# 20717.net
KiCad netlist of a schematic drawn in Altium Designer
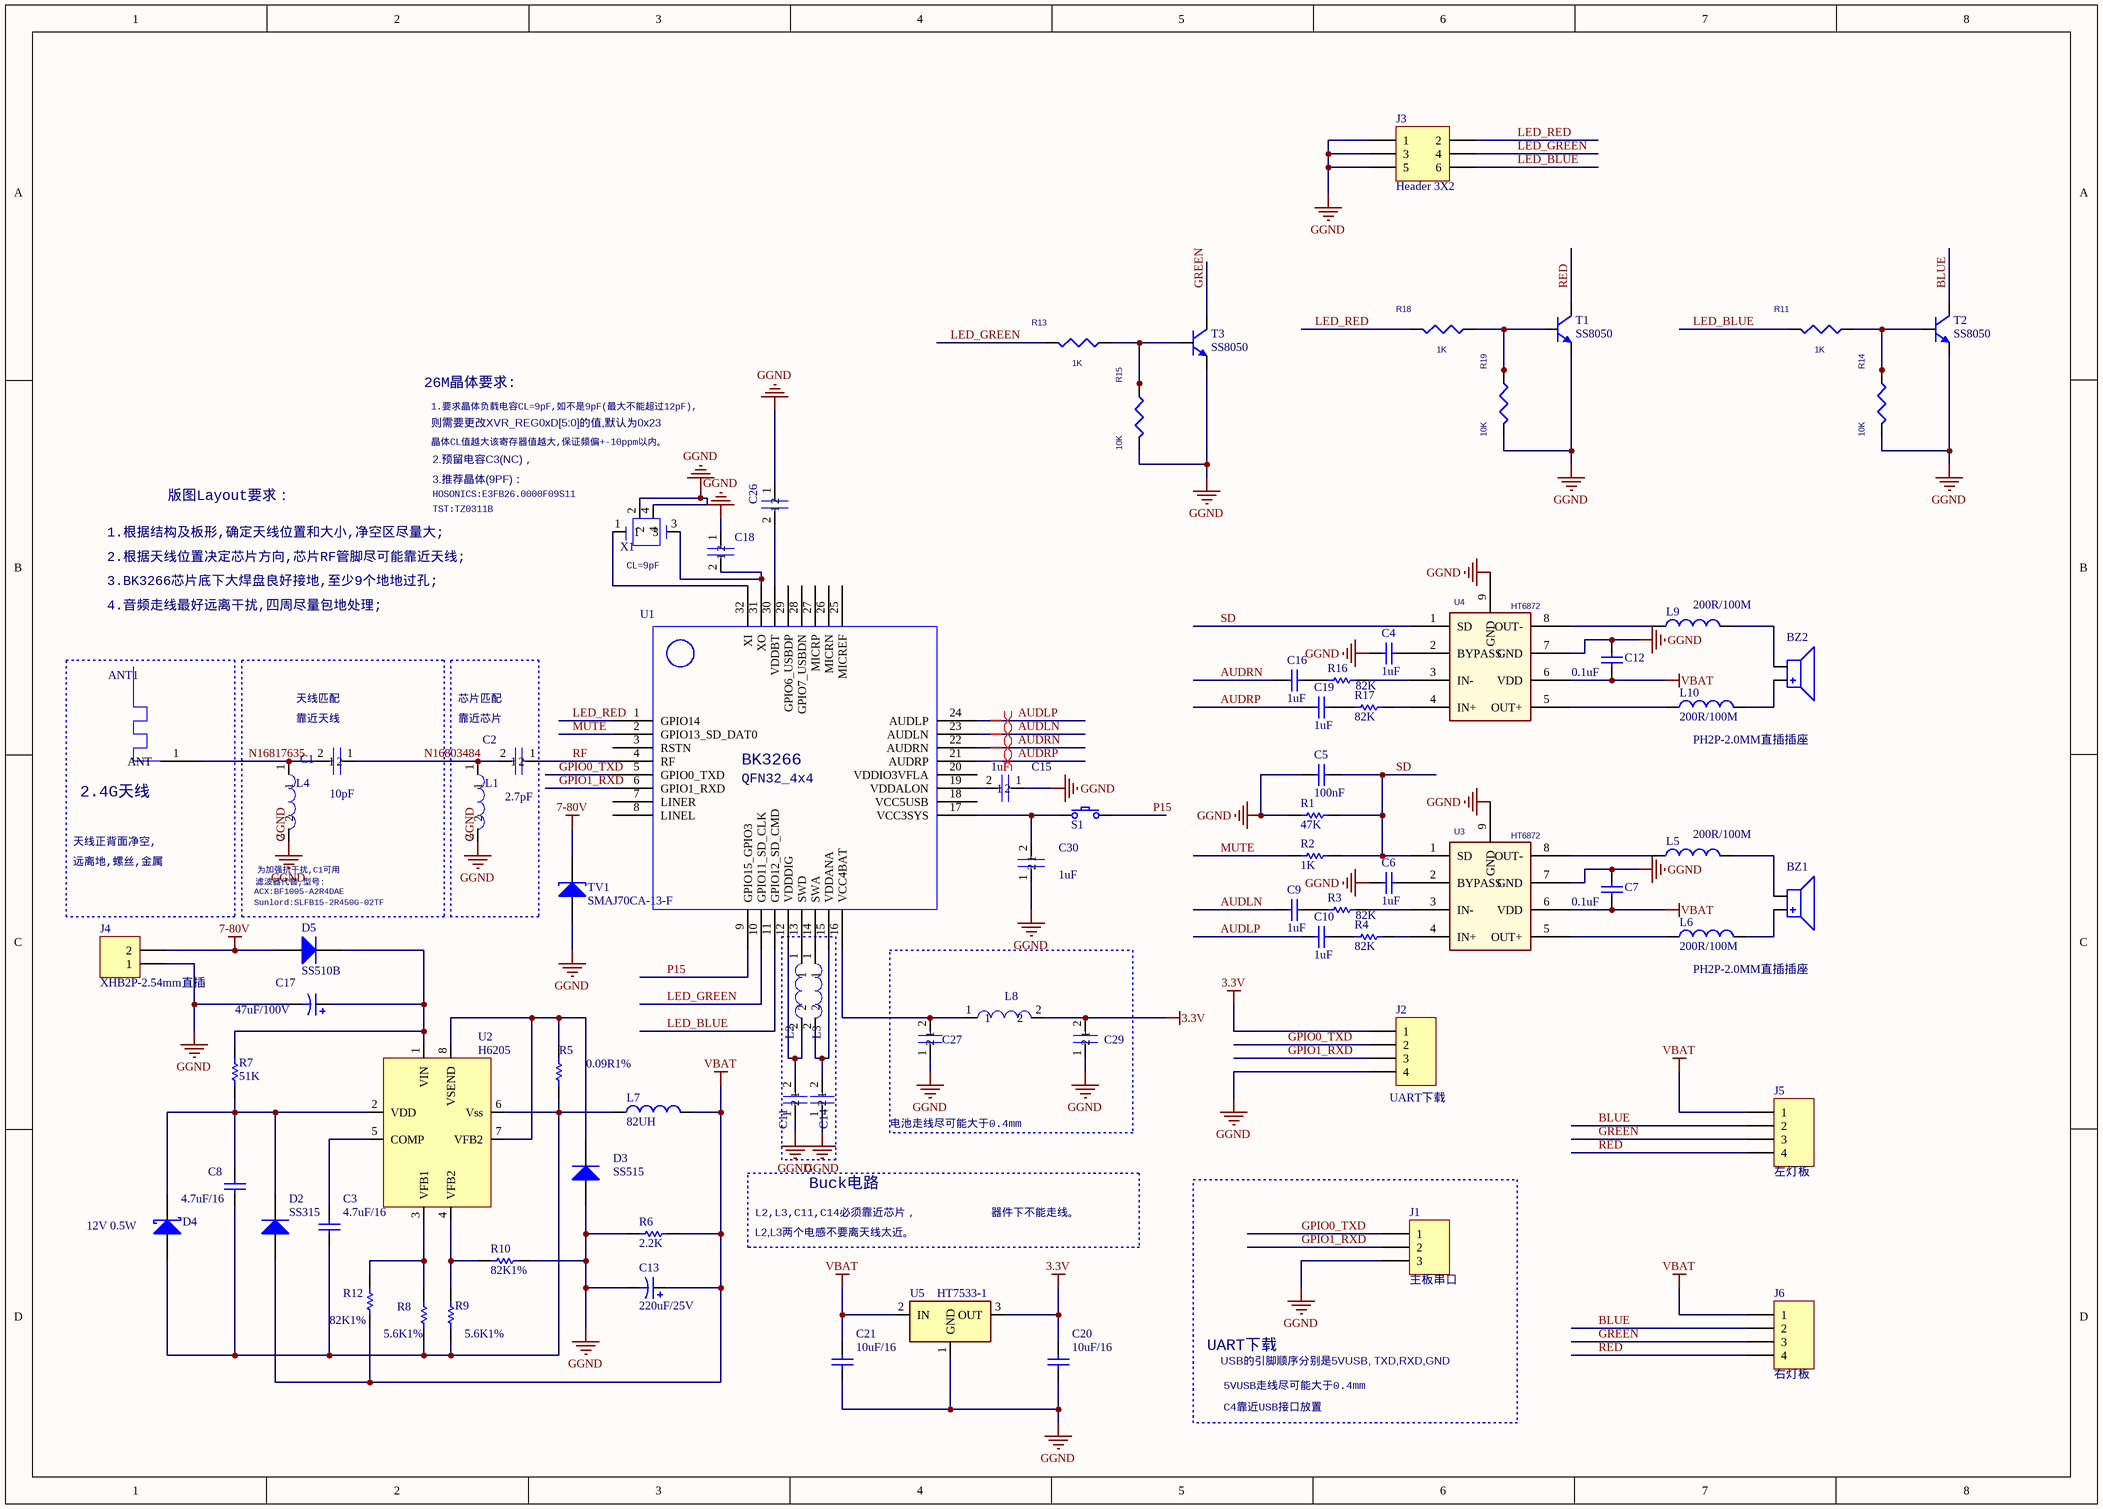
[diagram p0: 平衡车双声20717.SchDoc]

(export (version "E")
  (design (tool "Eeschema 10.0.6"))
  (components
    (comp (ref "ANT1") (value "ANT_2G4") (footprint "BT_NAMI_2") (libsource (lib "*") (part "ANT_2G4")))
    (comp (ref "BZ1")
      (value "PH2P-2.0MM直插插座")
      (footprint "2PIN-2.0")
      (description "Buzzer")
      (libsource (lib "MyLibrary") (part "BUZZER"))
    )
    (comp (ref "BZ2")
      (value "PH2P-2.0MM直插插座")
      (footprint "2PIN-2.0")
      (description "Buzzer")
      (libsource (lib "MyLibrary") (part "BUZZER"))
    )
    (comp (ref "C1")
      (value "10pF")
      (footprint "LC-0603_C")
      (fields (field (name "MANUFACTURER") "AVX") (field (name "MANUFACTURER_PART_NUMBER") "0805ZC105KAT2A"))
      (libsource (lib "*") (part "C0603_1"))
    )
    (comp (ref "C2")
      (value "2.7pF")
      (footprint "LC-0603_C")
      (fields (field (name "MANUFACTURER") "AVX") (field (name "MANUFACTURER_PART_NUMBER") "0805ZC105KAT2A"))
      (libsource (lib "*") (part "C0603_1"))
    )
    (comp (ref "C3")
      (value "4.7uF/16")
      (footprint "LC-0805_C")
      (description "Capacitor")
      (fields (field (name "PUBLISHER") "Altium Limited"))
      (libsource (lib "Miscellaneous Devices") (part "Cap"))
    )
    (comp (ref "C4")
      (value "1uF")
      (footprint "LC-0603_C")
      (description "Capacitor")
      (fields (field (name "PUBLISHER") "Altium Limited"))
      (libsource (lib "Miscellaneous Devices") (part "Cap"))
    )
    (comp (ref "C5")
      (value "100nF")
      (footprint "LC-0603_C")
      (description "Capacitor")
      (fields (field (name "PUBLISHER") "Altium Limited"))
      (libsource (lib "Miscellaneous Devices") (part "Cap"))
    )
    (comp (ref "C6")
      (value "1uF")
      (footprint "LC-0603_C")
      (description "Capacitor")
      (fields (field (name "PUBLISHER") "Altium Limited"))
      (libsource (lib "Miscellaneous Devices") (part "Cap"))
    )
    (comp (ref "C7")
      (value "0.1uF")
      (footprint "LC-0603_C")
      (description "Capacitor")
      (fields (field (name "PUBLISHER") "Altium Limited"))
      (libsource (lib "Miscellaneous Devices") (part "Cap"))
    )
    (comp (ref "C8")
      (value "4.7uF/16")
      (footprint "LC-0805_C")
      (description "Capacitor")
      (fields (field (name "PUBLISHER") "Altium Limited"))
      (libsource (lib "Miscellaneous Devices") (part "Cap"))
    )
    (comp (ref "C9")
      (value "1uF")
      (footprint "LC-0603_C")
      (description "Capacitor")
      (fields (field (name "PUBLISHER") "Altium Limited"))
      (libsource (lib "Miscellaneous Devices") (part "Cap"))
    )
    (comp (ref "C10")
      (value "1uF")
      (footprint "LC-0603_C")
      (description "Capacitor")
      (fields (field (name "PUBLISHER") "Altium Limited"))
      (libsource (lib "Miscellaneous Devices") (part "Cap"))
    )
    (comp (ref "C11")
      (value "4.7uF/0603")
      (footprint "LC-0603_C")
      (fields (field (name "MANUFACTURER") "AVX") (field (name "MANUFACTURER_PART_NUMBER") "06035C103KAt2A"))
      (libsource (lib "*") (part "AVX__1.01_UF_0603"))
    )
    (comp (ref "C12")
      (value "0.1uF")
      (footprint "LC-0603_C")
      (description "Capacitor")
      (fields (field (name "PUBLISHER") "Altium Limited"))
      (libsource (lib "Miscellaneous Devices") (part "Cap"))
    )
    (comp (ref "C13")
      (value "220uF/25V")
      (footprint "R3.5/8")
      (description "Polarized Capacitor (Radial)")
      (fields (field (name "PUBLISHER") "Altium Limited"))
      (libsource (lib "Miscellaneous Devices") (part "Cap Pol1"))
    )
    (comp (ref "C14")
      (value "4.7uF/0603")
      (footprint "LC-0603_C")
      (fields (field (name "MANUFACTURER") "AVX") (field (name "MANUFACTURER_PART_NUMBER") "06035C103KAt2A"))
      (libsource (lib "*") (part "AVX__1.01_UF_0603"))
    )
    (comp (ref "C15")
      (value "1uF")
      (footprint "LC-0603_C")
      (fields (field (name "MANUFACTURER") "AVX") (field (name "MANUFACTURER_PART_NUMBER") "0805ZC105KAT2A"))
      (libsource (lib "*") (part "C0603_1"))
    )
    (comp (ref "C16")
      (value "1uF")
      (footprint "LC-0603_C")
      (description "Capacitor")
      (fields (field (name "PUBLISHER") "Altium Limited"))
      (libsource (lib "Miscellaneous Devices") (part "Cap"))
    )
    (comp (ref "C17")
      (value "47uF/100V")
      (footprint "R3.5/8_1")
      (description "Polarized Capacitor (Radial)")
      (fields (field (name "PUBLISHER") "Altium Limited"))
      (libsource (lib "Miscellaneous Devices") (part "Cap Pol1"))
    )
    (comp (ref "C18")
      (value "10pF")
      (footprint "LC-0603_C")
      (fields (field (name "MANUFACTURER") "AVX") (field (name "MANUFACTURER_PART_NUMBER") "0805ZC105KAT2A"))
      (libsource (lib "*") (part "C0603_1"))
    )
    (comp (ref "C19")
      (value "1uF")
      (footprint "LC-0603_C")
      (description "Capacitor")
      (fields (field (name "PUBLISHER") "Altium Limited"))
      (libsource (lib "Miscellaneous Devices") (part "Cap"))
    )
    (comp (ref "C20")
      (value "10uF/16")
      (footprint "LC-0805_C")
      (description "Capacitor")
      (fields (field (name "PUBLISHER") "Altium Limited"))
      (libsource (lib "Miscellaneous Devices") (part "Cap"))
    )
    (comp (ref "C21")
      (value "10uF/16")
      (footprint "LC-0805_C")
      (description "Capacitor")
      (fields (field (name "PUBLISHER") "Altium Limited"))
      (libsource (lib "Miscellaneous Devices") (part "Cap"))
    )
    (comp (ref "C26")
      (value "1uF")
      (footprint "LC-0603_C")
      (fields (field (name "MANUFACTURER") "AVX") (field (name "MANUFACTURER_PART_NUMBER") "0805ZC105KAT2A"))
      (libsource (lib "*") (part "C0603_1"))
    )
    (comp (ref "C27")
      (value "0.1uF")
      (footprint "LC-0603_C")
      (fields (field (name "MANUFACTURER") "AVX") (field (name "MANUFACTURER_PART_NUMBER") "06035C103KAt2A"))
      (libsource (lib "*") (part "AVX__1.01_UF_0603"))
    )
    (comp (ref "C29")
      (value "0.1uF")
      (footprint "LC-0603_C")
      (fields (field (name "MANUFACTURER") "AVX") (field (name "MANUFACTURER_PART_NUMBER") "06035C103KAt2A"))
      (libsource (lib "*") (part "AVX__1.01_UF_0603"))
    )
    (comp (ref "C30")
      (value "1uF")
      (footprint "LC-0603_C")
      (fields (field (name "MANUFACTURER") "AVX") (field (name "MANUFACTURER_PART_NUMBER") "0805ZC105KAT2A"))
      (libsource (lib "*") (part "C0603_1"))
    )
    (comp (ref "D2")
      (value "SS315")
      (footprint "DO-214AA")
      (description "3 Amp General Purpose Rectifier")
      (fields (field (name "PUBLISHER") "Altium Limited"))
      (libsource (lib "Miscellaneous Devices") (part "Diode 1N5402"))
    )
    (comp (ref "D3")
      (value "SS515")
      (footprint "DO-214AA")
      (description "3 Amp General Purpose Rectifier")
      (fields (field (name "PUBLISHER") "Altium Limited"))
      (libsource (lib "Miscellaneous Devices") (part "Diode 1N5402"))
    )
    (comp (ref "D4")
      (value "12V 0.5W")
      (footprint "LL34/SOD-80")
      (description "Schottky Diode")
      (fields (field (name "PUBLISHER") "Altium Limited"))
      (libsource (lib "Miscellaneous Devices") (part "D Schottky"))
    )
    (comp (ref "D5")
      (value "SS510B")
      (footprint "DO-214AA")
      (description "3 Amp General Purpose Rectifier")
      (fields (field (name "PUBLISHER") "Altium Limited"))
      (libsource (lib "Miscellaneous Devices") (part "Diode 1N5402"))
    )
    (comp (ref "J1")
      (value "主板串口")
      (footprint "3PIN-2.0")
      (description "Header, 3-Pin")
      (fields (field (name "PUBLISHER") "Altium Limited"))
      (libsource (lib "Miscellaneous Connectors") (part "Header 3"))
    )
    (comp (ref "J2")
      (value "UART下载")
      (footprint "4P-2.0")
      (description "Header, 4-Pin")
      (fields (field (name "PUBLISHER") "Altium Limited"))
      (libsource (lib "保险箱STM32") (part "Header 4"))
    )
    (comp (ref "J3")
      (value "Header 3X2")
      (footprint "3P*2-2.0")
      (description "Header, 3-Pin, Dual row")
      (fields (field (name "PUBLISHER") "Altium Limited"))
      (libsource (lib "Miscellaneous Connectors") (part "Header 3X2"))
    )
    (comp (ref "J4")
      (value "XHB2P-2.54mm直插")
      (footprint "2P-2.5")
      (description "Header, 2-Pin")
      (fields (field (name "PUBLISHER") "Altium Limited"))
      (libsource (lib "保险箱STM32") (part "Header 2"))
    )
    (comp (ref "J5")
      (value "左灯板")
      (footprint "4PIN-2.0")
      (description "Header, 4-Pin")
      (fields (field (name "PUBLISHER") "Altium Limited"))
      (libsource (lib "Miscellaneous Connectors") (part "Header 4"))
    )
    (comp (ref "J6")
      (value "右灯板")
      (footprint "4PIN-2.0")
      (description "Header, 4-Pin")
      (fields (field (name "PUBLISHER") "Altium Limited"))
      (libsource (lib "Miscellaneous Connectors") (part "Header 4"))
    )
    (comp (ref "L1")
      (value "NC")
      (footprint "LC-0603_L")
      (fields
        (field (name "MANUFACTURER") "COILCRAFT")
        (field (name "MANUFACTURER_PART_NUMBER") "0805HS-030TMBC")
      )
      (libsource (lib "") (part "INDUCTOR_3NH_0603_1_1"))
    )
    (comp (ref "L2")
      (value "INDUCTOR_3NH_0603_1")
      (footprint "0805L")
      (fields
        (field (name "MANUFACTURER") "COILCRAFT")
        (field (name "MANUFACTURER_PART_NUMBER") "0805HS-030TMBC")
      )
      (libsource (lib "*") (part "INDUCTOR_3NH_0603_1"))
    )
    (comp (ref "L3")
      (value "INDUCTOR_3NH_0603_1")
      (footprint "0805L")
      (fields
        (field (name "MANUFACTURER") "COILCRAFT")
        (field (name "MANUFACTURER_PART_NUMBER") "0805HS-030TMBC")
      )
      (libsource (lib "") (part "INDUCTOR_3NH_0603_1_1"))
    )
    (comp (ref "L4")
      (value "NC")
      (footprint "LC-0603_L")
      (fields
        (field (name "MANUFACTURER") "COILCRAFT")
        (field (name "MANUFACTURER_PART_NUMBER") "0805HS-030TMBC")
      )
      (libsource (lib "") (part "INDUCTOR_3NH_0603_1_1"))
    )
    (comp (ref "L5")
      (value "200R/100M")
      (footprint "LC-0603_L")
      (description "Inductor")
      (fields (field (name "PUBLISHER") "Altium Limited"))
      (libsource (lib "Miscellaneous Devices") (part "Inductor"))
    )
    (comp (ref "L6")
      (value "200R/100M")
      (footprint "LC-0603_L")
      (description "Inductor")
      (fields (field (name "PUBLISHER") "Altium Limited"))
      (libsource (lib "Miscellaneous Devices") (part "Inductor"))
    )
    (comp (ref "L7")
      (value "82UH")
      (footprint "CD104")
      (description "Inductor")
      (fields (field (name "PUBLISHER") "Altium Limited"))
      (libsource (lib "Miscellaneous Devices") (part "Inductor"))
    )
    (comp (ref "L8")
      (value "INDUCTOR_3NH_0603_1")
      (footprint "0805L")
      (fields
        (field (name "MANUFACTURER") "COILCRAFT")
        (field (name "MANUFACTURER_PART_NUMBER") "0805HS-030TMBC")
      )
      (libsource (lib "") (part "INDUCTOR_3NH_0603_1_1"))
    )
    (comp (ref "L9")
      (value "200R/100M")
      (footprint "LC-0603_L")
      (description "Inductor")
      (fields (field (name "PUBLISHER") "Altium Limited"))
      (libsource (lib "Miscellaneous Devices") (part "Inductor"))
    )
    (comp (ref "L10")
      (value "200R/100M")
      (footprint "LC-0603_L")
      (description "Inductor")
      (fields (field (name "PUBLISHER") "Altium Limited"))
      (libsource (lib "Miscellaneous Devices") (part "Inductor"))
    )
    (comp (ref "R1")
      (value "47K")
      (footprint "LC-0603_R")
      (description "Resistor")
      (fields (field (name "PUBLISHER") "Altium Limited"))
      (libsource (lib "Miscellaneous Devices") (part "Res1"))
    )
    (comp (ref "R2")
      (value "1K")
      (footprint "LC-0603_R")
      (description "Resistor")
      (fields (field (name "PUBLISHER") "Altium Limited"))
      (libsource (lib "Miscellaneous Devices") (part "Res1"))
    )
    (comp (ref "R3")
      (value "82K")
      (footprint "LC-0603_R")
      (description "Resistor")
      (fields (field (name "PUBLISHER") "Altium Limited"))
      (libsource (lib "Miscellaneous Devices") (part "Res1"))
    )
    (comp (ref "R4")
      (value "82K")
      (footprint "LC-0603_R")
      (description "Resistor")
      (fields (field (name "PUBLISHER") "Altium Limited"))
      (libsource (lib "Miscellaneous Devices") (part "Res1"))
    )
    (comp (ref "R5")
      (value "0.09R1%")
      (footprint "LC-1206_R")
      (description "Resistor")
      (fields (field (name "PUBLISHER") "Altium Limited"))
      (libsource (lib "Miscellaneous Devices") (part "Res1"))
    )
    (comp (ref "R6")
      (value "2.2K")
      (footprint "LC-0603_R")
      (description "Resistor")
      (fields (field (name "PUBLISHER") "Altium Limited"))
      (libsource (lib "Miscellaneous Devices") (part "Res1"))
    )
    (comp (ref "R7")
      (value "51K")
      (footprint "LC-0603_R")
      (description "Resistor")
      (fields (field (name "PUBLISHER") "Altium Limited"))
      (libsource (lib "Miscellaneous Devices") (part "Res1"))
    )
    (comp (ref "R8")
      (value "5.6K1%")
      (footprint "LC-0603_R")
      (description "Resistor")
      (fields (field (name "PUBLISHER") "Altium Limited"))
      (libsource (lib "Miscellaneous Devices") (part "Res1"))
    )
    (comp (ref "R9")
      (value "5.6K1%")
      (footprint "LC-0603_R")
      (description "Resistor")
      (fields (field (name "PUBLISHER") "Altium Limited"))
      (libsource (lib "Miscellaneous Devices") (part "Res1"))
    )
    (comp (ref "R10")
      (value "82K1%")
      (footprint "LC-0603_R")
      (description "Resistor")
      (fields (field (name "PUBLISHER") "Altium Limited"))
      (libsource (lib "Miscellaneous Devices") (part "Res1"))
    )
    (comp (ref "R11") (value "1K") (footprint "LC-0603_R") (libsource (lib "*") (part "R_Dup1")))
    (comp (ref "R12")
      (value "82K1%")
      (footprint "LC-0603_R")
      (description "Resistor")
      (fields (field (name "PUBLISHER") "Altium Limited"))
      (libsource (lib "Miscellaneous Devices") (part "Res1"))
    )
    (comp (ref "R13") (value "1K") (footprint "LC-0603_R") (libsource (lib "*") (part "R_Dup1")))
    (comp (ref "R14") (value "10K") (footprint "LC-0603_R") (libsource (lib "*") (part "R_Dup1")))
    (comp (ref "R15") (value "10K") (footprint "LC-0603_R") (libsource (lib "*") (part "R_Dup1")))
    (comp (ref "R16")
      (value "82K")
      (footprint "LC-0603_R")
      (description "Resistor")
      (fields (field (name "PUBLISHER") "Altium Limited"))
      (libsource (lib "Miscellaneous Devices") (part "Res1"))
    )
    (comp (ref "R17")
      (value "82K")
      (footprint "LC-0603_R")
      (description "Resistor")
      (fields (field (name "PUBLISHER") "Altium Limited"))
      (libsource (lib "Miscellaneous Devices") (part "Res1"))
    )
    (comp (ref "R18") (value "1K") (footprint "LC-0603_R") (libsource (lib "*") (part "R_Dup1")))
    (comp (ref "R19") (value "10K") (footprint "LC-0603_R") (libsource (lib "*") (part "R_Dup1")))
    (comp (ref "S1")
      (value "SW")
      (footprint "KEY_5.2*3.7*6.4")
      (description "Switch")
      (libsource (lib "保险箱STM32") (part "SW"))
    )
    (comp (ref "T1")
      (value "SS8050")
      (footprint "SOT-23-3L")
      (description "Bipolar Junction Transistor")
      (libsource (lib "MyLibrary") (part "NPN_BJT"))
    )
    (comp (ref "T2")
      (value "SS8050")
      (footprint "SOT-23-3L")
      (description "Bipolar Junction Transistor")
      (libsource (lib "MyLibrary") (part "NPN_BJT"))
    )
    (comp (ref "T3")
      (value "SS8050")
      (footprint "SOT-23-3L")
      (description "Bipolar Junction Transistor")
      (libsource (lib "MyLibrary") (part "NPN_BJT"))
    )
    (comp (ref "TV1")
      (value "SMAJ70CA-13-F")
      (footprint "DO-214AA")
      (description "Tunnel Diode - RLC Model")
      (fields (field (name "PUBLISHER") "Altium Limited"))
      (libsource (lib "Miscellaneous Devices") (part "D Tunnel1"))
    )
    (comp (ref "U1")
      (value "BK3266_QFN32_5")
      (footprint "QFN32_4*4*0.4")
      (libsource (lib "*") (part "BK3266_QFN32_5"))
    )
    (comp (ref "U2") (value "H6205") (footprint "ESOP8") (libsource (lib "平衡车+蓝牙模块") (part "H6205")))
    (comp (ref "U3") (value "HT6872") (footprint "SOP8-LW") (libsource (lib "*") (part "AM24LC02_0")))
    (comp (ref "U4") (value "HT6872") (footprint "SOP8-LW") (libsource (lib "*") (part "AM24LC02_0")))
    (comp (ref "U5") (value "HT7533-1") (footprint "SOT-89-3") (libsource (lib "*") (part "XC6206P302M")))
    (comp (ref "X1") (value "XTAL_16MHZ") (footprint "XTAL3225") (libsource (lib "*") (part "XTAL_16MHZ")))
  )
  (nets
    (net (code "1") (name "/AUDLN") (class "Default")
      (node (ref "C9") (pin "1") (pinfunction "1_1") (pintype "passive"))
      (node (ref "U1") (pin "23") (pinfunction "AUDLN_23") (pintype "passive"))
    )
    (net (code "2") (name "/AUDLP") (class "Default")
      (node (ref "C10") (pin "1") (pinfunction "1_1") (pintype "passive"))
      (node (ref "U1") (pin "24") (pinfunction "AUDLP_24") (pintype "passive"))
    )
    (net (code "3") (name "/AUDRN") (class "Default")
      (node (ref "C16") (pin "1") (pinfunction "1_1") (pintype "passive"))
      (node (ref "U1") (pin "22") (pinfunction "AUDRN_22") (pintype "passive"))
    )
    (net (code "4") (name "/AUDRP") (class "Default")
      (node (ref "C19") (pin "1") (pinfunction "1_1") (pintype "passive"))
      (node (ref "U1") (pin "21") (pinfunction "AUDRP_21") (pintype "passive"))
    )
    (net (code "5") (name "/BLUE") (class "Default")
      (node (ref "J5") (pin "2") (pinfunction "2_2") (pintype "passive"))
      (node (ref "J6") (pin "2") (pinfunction "2_2") (pintype "passive"))
      (node (ref "T2") (pin "3") (pinfunction "3_3") (pintype "passive"))
    )
    (net (code "6") (name "/GPIO0_TXD") (class "Default")
      (node (ref "J1") (pin "1") (pinfunction "1_1") (pintype "passive"))
      (node (ref "J2") (pin "2") (pinfunction "2_2") (pintype "passive"))
      (node (ref "U1") (pin "5") (pinfunction "GPIO0_TXD_5") (pintype "passive"))
    )
    (net (code "7") (name "/GPIO1_RXD") (class "Default")
      (node (ref "J1") (pin "2") (pinfunction "2_2") (pintype "passive"))
      (node (ref "J2") (pin "3") (pinfunction "3_3") (pintype "passive"))
      (node (ref "U1") (pin "6") (pinfunction "GPIO1_RXD_6") (pintype "passive"))
    )
    (net (code "8") (name "/GREEN") (class "Default")
      (node (ref "J5") (pin "3") (pinfunction "3_3") (pintype "passive"))
      (node (ref "J6") (pin "3") (pinfunction "3_3") (pintype "passive"))
      (node (ref "T3") (pin "3") (pinfunction "3_3") (pintype "passive"))
    )
    (net (code "9") (name "/LED_BLUE") (class "Default")
      (node (ref "J3") (pin "6") (pinfunction "6_6") (pintype "passive"))
      (node (ref "R11") (pin "2") (pinfunction "2_2") (pintype "passive"))
      (node (ref "U1") (pin "11") (pinfunction "GPIO12_SD_CMD_11") (pintype "passive"))
    )
    (net (code "10") (name "/LED_GREEN") (class "Default")
      (node (ref "J3") (pin "4") (pinfunction "4_4") (pintype "passive"))
      (node (ref "R13") (pin "2") (pinfunction "2_2") (pintype "passive"))
      (node (ref "U1") (pin "10") (pinfunction "GPIO11_SD_CLK_10") (pintype "passive"))
    )
    (net (code "11") (name "/LED_RED") (class "Default")
      (node (ref "J3") (pin "2") (pinfunction "2_2") (pintype "passive"))
      (node (ref "R18") (pin "2") (pinfunction "2_2") (pintype "passive"))
      (node (ref "U1") (pin "1") (pinfunction "GPIO14_1") (pintype "passive"))
    )
    (net (code "12") (name "/MUTE") (class "Default")
      (node (ref "R2") (pin "1") (pinfunction "1_1") (pintype "passive"))
      (node (ref "U1") (pin "2") (pinfunction "GPIO13_SD_DAT0_2") (pintype "passive"))
    )
    (net (code "13") (name "/N16803484") (class "Default")
      (node (ref "C1") (pin "1") (pinfunction "1_1") (pintype "passive"))
      (node (ref "C2") (pin "2") (pinfunction "2_2") (pintype "passive"))
      (node (ref "L1") (pin "1") (pinfunction "1_1") (pintype "passive"))
    )
    (net (code "14") (name "/N16817635") (class "Default")
      (node (ref "ANT1") (pin "1") (pinfunction "ANT_1") (pintype "passive"))
      (node (ref "C1") (pin "2") (pinfunction "2_2") (pintype "passive"))
      (node (ref "L4") (pin "1") (pinfunction "1_1") (pintype "passive"))
    )
    (net (code "15") (name "/P15") (class "Default")
      (node (ref "S1") (pin "2") (pintype "passive"))
      (node (ref "U1") (pin "9") (pinfunction "GPIO15_GPIO3_9") (pintype "passive"))
    )
    (net (code "16") (name "/RED") (class "Default")
      (node (ref "J5") (pin "4") (pinfunction "4_4") (pintype "passive"))
      (node (ref "J6") (pin "4") (pinfunction "4_4") (pintype "passive"))
      (node (ref "T1") (pin "3") (pinfunction "3_3") (pintype "passive"))
    )
    (net (code "17") (name "/RF") (class "Default")
      (node (ref "C2") (pin "1") (pinfunction "1_1") (pintype "passive"))
      (node (ref "U1") (pin "4") (pinfunction "RF_4") (pintype "passive"))
    )
    (net (code "18") (name "/SD") (class "Default")
      (node (ref "C5") (pin "2") (pinfunction "2_2") (pintype "passive"))
      (node (ref "R1") (pin "2") (pinfunction "2_2") (pintype "passive"))
      (node (ref "R2") (pin "2") (pinfunction "2_2") (pintype "passive"))
      (node (ref "U3") (pin "1") (pinfunction "SD_1") (pintype "passive"))
      (node (ref "U4") (pin "1") (pinfunction "SD_1") (pintype "passive"))
    )
    (net (code "19") (name "3.3V") (class "Default")
      (node (ref "C20") (pin "2") (pinfunction "2_2") (pintype "passive"))
      (node (ref "C29") (pin "2") (pinfunction "2_2") (pintype "passive"))
      (node (ref "J2") (pin "1") (pinfunction "1_1") (pintype "passive"))
      (node (ref "L8") (pin "2") (pinfunction "2_2") (pintype "passive"))
      (node (ref "U5") (pin "3") (pinfunction "OUT_3") (pintype "passive"))
    )
    (net (code "20") (name "7-80V") (class "Default")
      (node (ref "D5") (pin "1") (pinfunction "A_1") (pintype "passive"))
      (node (ref "J4") (pin "2") (pinfunction "2_2") (pintype "passive"))
      (node (ref "TV1") (pin "2") (pinfunction "K_2") (pintype "passive"))
    )
    (net (code "21") (name "GGND") (class "Default")
      (node (ref "C11") (pin "1") (pinfunction "1_1") (pintype "passive"))
      (node (ref "C12") (pin "2") (pinfunction "2_2") (pintype "passive"))
      (node (ref "C13") (pin "2") (pinfunction "2_2") (pintype "passive"))
      (node (ref "C14") (pin "1") (pinfunction "1_1") (pintype "passive"))
      (node (ref "C15") (pin "1") (pinfunction "1_1") (pintype "passive"))
      (node (ref "C17") (pin "2") (pinfunction "2_2") (pintype "passive"))
      (node (ref "C18") (pin "1") (pinfunction "1_1") (pintype "passive"))
      (node (ref "C20") (pin "1") (pinfunction "1_1") (pintype "passive"))
      (node (ref "C21") (pin "1") (pinfunction "1_1") (pintype "passive"))
      (node (ref "C26") (pin "1") (pinfunction "1_1") (pintype "passive"))
      (node (ref "C27") (pin "1") (pinfunction "1_1") (pintype "passive"))
      (node (ref "C29") (pin "1") (pinfunction "1_1") (pintype "passive"))
      (node (ref "C30") (pin "1") (pinfunction "1_1") (pintype "passive"))
      (node (ref "C4") (pin "1") (pinfunction "1_1") (pintype "passive"))
      (node (ref "C5") (pin "1") (pinfunction "1_1") (pintype "passive"))
      (node (ref "C6") (pin "1") (pinfunction "1_1") (pintype "passive"))
      (node (ref "C7") (pin "2") (pinfunction "2_2") (pintype "passive"))
      (node (ref "D3") (pin "1") (pinfunction "A_1") (pintype "passive"))
      (node (ref "J1") (pin "3") (pinfunction "3_3") (pintype "passive"))
      (node (ref "J2") (pin "4") (pinfunction "4_4") (pintype "passive"))
      (node (ref "J3") (pin "1") (pinfunction "1_1") (pintype "passive"))
      (node (ref "J3") (pin "3") (pinfunction "3_3") (pintype "passive"))
      (node (ref "J3") (pin "5") (pinfunction "5_5") (pintype "passive"))
      (node (ref "J4") (pin "1") (pinfunction "1_1") (pintype "passive"))
      (node (ref "L1") (pin "2") (pinfunction "2_2") (pintype "passive"))
      (node (ref "L4") (pin "2") (pinfunction "2_2") (pintype "passive"))
      (node (ref "R1") (pin "1") (pinfunction "1_1") (pintype "passive"))
      (node (ref "R10") (pin "2") (pinfunction "2_2") (pintype "passive"))
      (node (ref "R14") (pin "2") (pinfunction "2_2") (pintype "passive"))
      (node (ref "R15") (pin "2") (pinfunction "2_2") (pintype "passive"))
      (node (ref "R19") (pin "2") (pinfunction "2_2") (pintype "passive"))
      (node (ref "R6") (pin "2") (pinfunction "2_2") (pintype "passive"))
      (node (ref "T1") (pin "2") (pinfunction "2_2") (pintype "passive"))
      (node (ref "T2") (pin "2") (pinfunction "2_2") (pintype "passive"))
      (node (ref "T3") (pin "2") (pinfunction "2_2") (pintype "passive"))
      (node (ref "TV1") (pin "1") (pinfunction "A_1") (pintype "passive"))
      (node (ref "U1") (pin "33") (pinfunction "GGND_33") (pintype "power_in"))
      (node (ref "U3") (pin "7") (pinfunction "GND_7") (pintype "passive"))
      (node (ref "U3") (pin "9") (pinfunction "GND_9") (pintype "passive"))
      (node (ref "U4") (pin "7") (pinfunction "GND_7") (pintype "passive"))
      (node (ref "U4") (pin "9") (pinfunction "GND_9") (pintype "passive"))
      (node (ref "U5") (pin "1") (pinfunction "GND_1") (pintype "passive"))
      (node (ref "X1") (pin "2") (pinfunction "2_2") (pintype "passive"))
      (node (ref "X1") (pin "4") (pinfunction "4_4") (pintype "passive"))
    )
    (net (code "22") (name "Net-(BZ1-Pad1)") (class "Default")
      (node (ref "BZ1") (pin "1") (pintype "passive"))
      (node (ref "L6") (pin "2") (pinfunction "2_2") (pintype "passive"))
    )
    (net (code "23") (name "Net-(BZ1-Pad2)") (class "Default")
      (node (ref "BZ1") (pin "2") (pintype "passive"))
      (node (ref "L5") (pin "2") (pinfunction "2_2") (pintype "passive"))
    )
    (net (code "24") (name "Net-(BZ2-Pad1)") (class "Default")
      (node (ref "BZ2") (pin "1") (pintype "passive"))
      (node (ref "L10") (pin "2") (pinfunction "2_2") (pintype "passive"))
    )
    (net (code "25") (name "Net-(BZ2-Pad2)") (class "Default")
      (node (ref "BZ2") (pin "2") (pintype "passive"))
      (node (ref "L9") (pin "2") (pinfunction "2_2") (pintype "passive"))
    )
    (net (code "26") (name "Net-(C9-Pad2)") (class "Default")
      (node (ref "C9") (pin "2") (pinfunction "2_2") (pintype "passive"))
      (node (ref "R3") (pin "1") (pinfunction "1_1") (pintype "passive"))
    )
    (net (code "27") (name "Net-(C10-Pad2)") (class "Default")
      (node (ref "C10") (pin "2") (pinfunction "2_2") (pintype "passive"))
      (node (ref "R4") (pin "1") (pinfunction "1_1") (pintype "passive"))
    )
    (net (code "28") (name "Net-(C16-Pad2)") (class "Default")
      (node (ref "C16") (pin "2") (pinfunction "2_2") (pintype "passive"))
      (node (ref "R16") (pin "1") (pinfunction "1_1") (pintype "passive"))
    )
    (net (code "29") (name "Net-(C19-Pad2)") (class "Default")
      (node (ref "C19") (pin "2") (pinfunction "2_2") (pintype "passive"))
      (node (ref "R17") (pin "1") (pinfunction "1_1") (pintype "passive"))
    )
    (net (code "30") (name "Net-(D2-K)") (class "Default")
      (node (ref "C8") (pin "2") (pinfunction "2_2") (pintype "passive"))
      (node (ref "D2") (pin "2") (pinfunction "K_2") (pintype "passive"))
      (node (ref "D4") (pin "2") (pinfunction "K_2") (pintype "passive"))
      (node (ref "R7") (pin "1") (pinfunction "1_1") (pintype "passive"))
      (node (ref "U2") (pin "2") (pinfunction "VDD_2") (pintype "passive"))
    )
    (net (code "31") (name "Net-(D3-K)") (class "Default")
      (node (ref "D3") (pin "2") (pinfunction "K_2") (pintype "passive"))
      (node (ref "R5") (pin "2") (pinfunction "2_2") (pintype "passive"))
      (node (ref "U2") (pin "7") (pinfunction "VFB2_7") (pintype "passive"))
      (node (ref "U2") (pin "8") (pinfunction "VSEND_8") (pintype "passive"))
    )
    (net (code "32") (name "Net-(D4-A)") (class "Default")
      (node (ref "C3") (pin "1") (pinfunction "1_1") (pintype "passive"))
      (node (ref "C8") (pin "1") (pinfunction "1_1") (pintype "passive"))
      (node (ref "D4") (pin "1") (pinfunction "A_1") (pintype "passive"))
      (node (ref "L7") (pin "1") (pinfunction "1_1") (pintype "passive"))
      (node (ref "R5") (pin "1") (pinfunction "1_1") (pintype "passive"))
      (node (ref "R8") (pin "2") (pinfunction "2_2") (pintype "passive"))
      (node (ref "R9") (pin "2") (pinfunction "2_2") (pintype "passive"))
      (node (ref "U2") (pin "6") (pinfunction "Vss_6") (pintype "passive"))
    )
    (net (code "33") (name "Net-(D5-K)") (class "Default")
      (node (ref "C17") (pin "1") (pinfunction "1_1") (pintype "passive"))
      (node (ref "D5") (pin "2") (pinfunction "K_2") (pintype "passive"))
      (node (ref "R7") (pin "2") (pinfunction "2_2") (pintype "passive"))
      (node (ref "U2") (pin "1") (pinfunction "VIN_1") (pintype "passive"))
    )
    (net (code "34") (name "Net-(R10-Pad1)") (class "Default")
      (node (ref "R10") (pin "1") (pinfunction "1_1") (pintype "passive"))
      (node (ref "R9") (pin "1") (pinfunction "1_1") (pintype "passive"))
      (node (ref "U2") (pin "4") (pinfunction "VFB2_4") (pintype "passive"))
    )
    (net (code "35") (name "Net-(R11-Pad1)") (class "Default")
      (node (ref "R11") (pin "1") (pinfunction "1_1") (pintype "passive"))
      (node (ref "R14") (pin "1") (pinfunction "1_1") (pintype "passive"))
      (node (ref "T2") (pin "1") (pinfunction "1_1") (pintype "passive"))
    )
    (net (code "36") (name "Net-(R13-Pad1)") (class "Default")
      (node (ref "R13") (pin "1") (pinfunction "1_1") (pintype "passive"))
      (node (ref "R15") (pin "1") (pinfunction "1_1") (pintype "passive"))
      (node (ref "T3") (pin "1") (pinfunction "1_1") (pintype "passive"))
    )
    (net (code "37") (name "Net-(R18-Pad1)") (class "Default")
      (node (ref "R18") (pin "1") (pinfunction "1_1") (pintype "passive"))
      (node (ref "R19") (pin "1") (pinfunction "1_1") (pintype "passive"))
      (node (ref "T1") (pin "1") (pinfunction "1_1") (pintype "passive"))
    )
    (net (code "38") (name "Net-(U1-SWA)") (class "Default")
      (node (ref "L3") (pin "1") (pinfunction "1_1") (pintype "passive"))
      (node (ref "U1") (pin "14") (pinfunction "SWA_14") (pintype "passive"))
    )
    (net (code "39") (name "Net-(U1-SWD)") (class "Default")
      (node (ref "L2") (pin "1") (pinfunction "1_1") (pintype "passive"))
      (node (ref "U1") (pin "13") (pinfunction "SWD_13") (pintype "passive"))
    )
    (net (code "40") (name "Net-(U1-VCC3SYS)") (class "Default")
      (node (ref "C30") (pin "2") (pinfunction "2_2") (pintype "passive"))
      (node (ref "S1") (pin "1") (pintype "passive"))
      (node (ref "U1") (pin "17") (pinfunction "VCC3SYS_17") (pintype "passive"))
    )
    (net (code "41") (name "Net-(U1-VCC4BAT)") (class "Default")
      (node (ref "C27") (pin "2") (pinfunction "2_2") (pintype "passive"))
      (node (ref "L8") (pin "1") (pinfunction "1_1") (pintype "passive"))
      (node (ref "U1") (pin "16") (pinfunction "VCC4BAT_16") (pintype "passive"))
    )
    (net (code "42") (name "Net-(U1-VDDALON)") (class "Default")
      (node (ref "C15") (pin "2") (pinfunction "2_2") (pintype "passive"))
      (node (ref "U1") (pin "19") (pinfunction "VDDALON_19") (pintype "passive"))
    )
    (net (code "43") (name "Net-(U1-VDDANA)") (class "Default")
      (node (ref "C14") (pin "2") (pinfunction "2_2") (pintype "passive"))
      (node (ref "L3") (pin "2") (pinfunction "2_2") (pintype "passive"))
      (node (ref "U1") (pin "15") (pinfunction "VDDANA_15") (pintype "passive"))
    )
    (net (code "44") (name "Net-(U1-VDDBT)") (class "Default")
      (node (ref "C26") (pin "2") (pinfunction "2_2") (pintype "passive"))
      (node (ref "U1") (pin "30") (pinfunction "VDDBT_30") (pintype "passive"))
    )
    (net (code "45") (name "Net-(U1-VDDDIG)") (class "Default")
      (node (ref "C11") (pin "2") (pinfunction "2_2") (pintype "passive"))
      (node (ref "L2") (pin "2") (pinfunction "2_2") (pintype "passive"))
      (node (ref "U1") (pin "12") (pinfunction "VDDDIG_12") (pintype "passive"))
    )
    (net (code "46") (name "Net-(U1-XI)") (class "Default")
      (node (ref "U1") (pin "32") (pinfunction "XI_32") (pintype "passive"))
      (node (ref "X1") (pin "1") (pinfunction "1_1") (pintype "passive"))
    )
    (net (code "47") (name "Net-(U1-XO)") (class "Default")
      (node (ref "C18") (pin "2") (pinfunction "2_2") (pintype "passive"))
      (node (ref "U1") (pin "31") (pinfunction "XO_31") (pintype "passive"))
      (node (ref "X1") (pin "3") (pinfunction "3_3") (pintype "passive"))
    )
    (net (code "48") (name "Net-(U2-COMP)") (class "Default")
      (node (ref "C3") (pin "2") (pinfunction "2_2") (pintype "passive"))
      (node (ref "U2") (pin "5") (pinfunction "COMP_5") (pintype "passive"))
    )
    (net (code "49") (name "Net-(U2-VFB1)") (class "Default")
      (node (ref "R12") (pin "2") (pinfunction "2_2") (pintype "passive"))
      (node (ref "R8") (pin "1") (pinfunction "1_1") (pintype "passive"))
      (node (ref "U2") (pin "3") (pinfunction "VFB1_3") (pintype "passive"))
    )
    (net (code "50") (name "Net-(U3-BYPASS)") (class "Default")
      (node (ref "C6") (pin "2") (pinfunction "2_2") (pintype "passive"))
      (node (ref "U3") (pin "2") (pinfunction "BYPASS_2") (pintype "passive"))
    )
    (net (code "51") (name "Net-(U3-IN+)") (class "Default")
      (node (ref "R4") (pin "2") (pinfunction "2_2") (pintype "passive"))
      (node (ref "U3") (pin "4") (pinfunction "IN+_4") (pintype "passive"))
    )
    (net (code "52") (name "Net-(U3-IN-)") (class "Default")
      (node (ref "R3") (pin "2") (pinfunction "2_2") (pintype "passive"))
      (node (ref "U3") (pin "3") (pinfunction "IN-_3") (pintype "passive"))
    )
    (net (code "53") (name "Net-(U3-OUT+)") (class "Default")
      (node (ref "L6") (pin "1") (pinfunction "1_1") (pintype "passive"))
      (node (ref "U3") (pin "5") (pinfunction "OUT+_5") (pintype "passive"))
    )
    (net (code "54") (name "Net-(U3-OUT-)") (class "Default")
      (node (ref "L5") (pin "1") (pinfunction "1_1") (pintype "passive"))
      (node (ref "U3") (pin "8") (pinfunction "OUT-_8") (pintype "passive"))
    )
    (net (code "55") (name "Net-(U4-BYPASS)") (class "Default")
      (node (ref "C4") (pin "2") (pinfunction "2_2") (pintype "passive"))
      (node (ref "U4") (pin "2") (pinfunction "BYPASS_2") (pintype "passive"))
    )
    (net (code "56") (name "Net-(U4-IN+)") (class "Default")
      (node (ref "R17") (pin "2") (pinfunction "2_2") (pintype "passive"))
      (node (ref "U4") (pin "4") (pinfunction "IN+_4") (pintype "passive"))
    )
    (net (code "57") (name "Net-(U4-IN-)") (class "Default")
      (node (ref "R16") (pin "2") (pinfunction "2_2") (pintype "passive"))
      (node (ref "U4") (pin "3") (pinfunction "IN-_3") (pintype "passive"))
    )
    (net (code "58") (name "Net-(U4-OUT+)") (class "Default")
      (node (ref "L10") (pin "1") (pinfunction "1_1") (pintype "passive"))
      (node (ref "U4") (pin "5") (pinfunction "OUT+_5") (pintype "passive"))
    )
    (net (code "59") (name "Net-(U4-OUT-)") (class "Default")
      (node (ref "L9") (pin "1") (pinfunction "1_1") (pintype "passive"))
      (node (ref "U4") (pin "8") (pinfunction "OUT-_8") (pintype "passive"))
    )
    (net (code "60") (name "VBAT") (class "Default")
      (node (ref "C12") (pin "1") (pinfunction "1_1") (pintype "passive"))
      (node (ref "C13") (pin "1") (pinfunction "1_1") (pintype "passive"))
      (node (ref "C21") (pin "2") (pinfunction "2_2") (pintype "passive"))
      (node (ref "C7") (pin "1") (pinfunction "1_1") (pintype "passive"))
      (node (ref "D2") (pin "1") (pinfunction "A_1") (pintype "passive"))
      (node (ref "J5") (pin "1") (pinfunction "1_1") (pintype "passive"))
      (node (ref "J6") (pin "1") (pinfunction "1_1") (pintype "passive"))
      (node (ref "L7") (pin "2") (pinfunction "2_2") (pintype "passive"))
      (node (ref "R12") (pin "1") (pinfunction "1_1") (pintype "passive"))
      (node (ref "R6") (pin "1") (pinfunction "1_1") (pintype "passive"))
      (node (ref "U3") (pin "6") (pinfunction "VDD_6") (pintype "passive"))
      (node (ref "U4") (pin "6") (pinfunction "VDD_6") (pintype "passive"))
      (node (ref "U5") (pin "2") (pinfunction "IN_2") (pintype "passive"))
    )
    (net (code "61") (name "unconnected-(U1-GPIO6_USBDP-Pad29)") (class "Default")
      (node (ref "U1") (pin "29") (pinfunction "GPIO6_USBDP_29") (pintype "passive"))
    )
    (net (code "62") (name "unconnected-(U1-GPIO7_USBDN-Pad28)") (class "Default")
      (node (ref "U1") (pin "28") (pinfunction "GPIO7_USBDN_28") (pintype "passive"))
    )
    (net (code "63") (name "unconnected-(U1-LINEL-Pad8)") (class "Default")
      (node (ref "U1") (pin "8") (pinfunction "LINEL_8") (pintype "passive"))
    )
    (net (code "64") (name "unconnected-(U1-LINER-Pad7)") (class "Default")
      (node (ref "U1") (pin "7") (pinfunction "LINER_7") (pintype "passive"))
    )
    (net (code "65") (name "unconnected-(U1-MICREF-Pad25)") (class "Default")
      (node (ref "U1") (pin "25") (pinfunction "MICREF_25") (pintype "passive"))
    )
    (net (code "66") (name "unconnected-(U1-MICRN-Pad26)") (class "Default")
      (node (ref "U1") (pin "26") (pinfunction "MICRN_26") (pintype "passive"))
    )
    (net (code "67") (name "unconnected-(U1-MICRP-Pad27)") (class "Default")
      (node (ref "U1") (pin "27") (pinfunction "MICRP_27") (pintype "passive"))
    )
    (net (code "68") (name "unconnected-(U1-RSTN-Pad3)") (class "Default")
      (node (ref "U1") (pin "3") (pinfunction "RSTN_3") (pintype "passive"))
    )
    (net (code "69") (name "unconnected-(U1-VCC5USB-Pad18)") (class "Default")
      (node (ref "U1") (pin "18") (pinfunction "VCC5USB_18") (pintype "passive"))
    )
    (net (code "70") (name "unconnected-(U1-VDDIO3VFLA-Pad20)") (class "Default")
      (node (ref "U1") (pin "20") (pinfunction "VDDIO3VFLA_20") (pintype "passive"))
    )
  )
)
